# QSFP_Jumper.net
KiCad netlist of a schematic drawn in Altium Designer
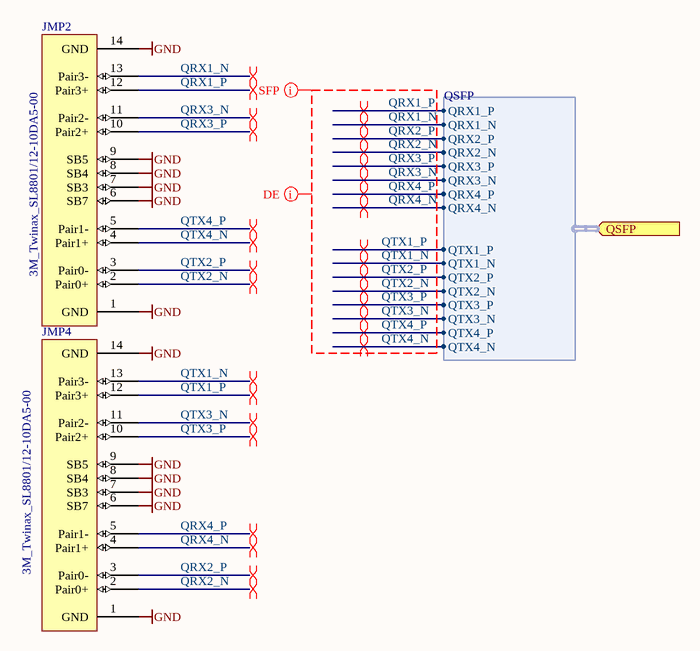
[diagram p0: QSFP_Jumper.SchDoc]

(export (version "E")
  (design (tool "Eeschema 10.0.6"))
  (components
    (comp (ref "JMP2")
      (value "3M_Twinax_SL8801/12-10DA5-00")
      (footprint "3M_Twinax_SL8801/12-10DA5-00")
      (libsource (lib "LIBRARY_SCH") (part "CBL_TWINAX_3M_4pairs_SB"))
    )
    (comp (ref "JMP4")
      (value "3M_Twinax_SL8801/12-10DA5-00")
      (footprint "3M_Twinax_SL8801/12-10DA5-00")
      (libsource (lib "LIBRARY_SCH") (part "CBL_TWINAX_3M_4pairs_SB"))
    )
  )
  (nets
    (net (code "2") (name "/QRX1_N") (class "Default")
      (node (ref "JMP2") (pin "13") (pinfunction "Pair3-_13") (pintype "bidirectional"))
    )
    (net (code "3") (name "/QRX1_P") (class "Default")
      (node (ref "JMP2") (pin "12") (pinfunction "Pair3+_12") (pintype "bidirectional"))
    )
    (net (code "4") (name "/QRX2_N") (class "Default")
      (node (ref "JMP4") (pin "2") (pinfunction "Pair0+_2") (pintype "bidirectional"))
    )
    (net (code "5") (name "/QRX2_P") (class "Default")
      (node (ref "JMP4") (pin "3") (pinfunction "Pair0-_3") (pintype "bidirectional"))
    )
    (net (code "6") (name "/QRX3_N") (class "Default")
      (node (ref "JMP2") (pin "11") (pinfunction "Pair2-_11") (pintype "bidirectional"))
    )
    (net (code "7") (name "/QRX3_P") (class "Default")
      (node (ref "JMP2") (pin "10") (pinfunction "Pair2+_10") (pintype "bidirectional"))
    )
    (net (code "8") (name "/QRX4_N") (class "Default")
      (node (ref "JMP4") (pin "4") (pinfunction "Pair1+_4") (pintype "bidirectional"))
    )
    (net (code "9") (name "/QRX4_P") (class "Default")
      (node (ref "JMP4") (pin "5") (pinfunction "Pair1-_5") (pintype "bidirectional"))
    )
    (net (code "10") (name "/QTX1_N") (class "Default")
      (node (ref "JMP4") (pin "13") (pinfunction "Pair3-_13") (pintype "bidirectional"))
    )
    (net (code "11") (name "/QTX1_P") (class "Default")
      (node (ref "JMP4") (pin "12") (pinfunction "Pair3+_12") (pintype "bidirectional"))
    )
    (net (code "12") (name "/QTX2_N") (class "Default")
      (node (ref "JMP2") (pin "2") (pinfunction "Pair0+_2") (pintype "bidirectional"))
    )
    (net (code "13") (name "/QTX2_P") (class "Default")
      (node (ref "JMP2") (pin "3") (pinfunction "Pair0-_3") (pintype "bidirectional"))
    )
    (net (code "14") (name "/QTX3_N") (class "Default")
      (node (ref "JMP4") (pin "11") (pinfunction "Pair2-_11") (pintype "bidirectional"))
    )
    (net (code "15") (name "/QTX3_P") (class "Default")
      (node (ref "JMP4") (pin "10") (pinfunction "Pair2+_10") (pintype "bidirectional"))
    )
    (net (code "16") (name "/QTX4_N") (class "Default")
      (node (ref "JMP2") (pin "4") (pinfunction "Pair1+_4") (pintype "bidirectional"))
    )
    (net (code "17") (name "/QTX4_P") (class "Default")
      (node (ref "JMP2") (pin "5") (pinfunction "Pair1-_5") (pintype "bidirectional"))
    )
    (net (code "19") (name "GND") (class "Default")
      (node (ref "JMP2") (pin "1") (pinfunction "GND_1") (pintype "power_in"))
      (node (ref "JMP2") (pin "14") (pinfunction "GND_14") (pintype "power_in"))
      (node (ref "JMP2") (pin "6") (pinfunction "SB7_6") (pintype "bidirectional"))
      (node (ref "JMP2") (pin "7") (pinfunction "SB3_7") (pintype "bidirectional"))
      (node (ref "JMP2") (pin "8") (pinfunction "SB4_8") (pintype "bidirectional"))
      (node (ref "JMP2") (pin "9") (pinfunction "SB5_9") (pintype "bidirectional"))
      (node (ref "JMP4") (pin "1") (pinfunction "GND_1") (pintype "power_in"))
      (node (ref "JMP4") (pin "14") (pinfunction "GND_14") (pintype "power_in"))
      (node (ref "JMP4") (pin "6") (pinfunction "SB7_6") (pintype "bidirectional"))
      (node (ref "JMP4") (pin "7") (pinfunction "SB3_7") (pintype "bidirectional"))
      (node (ref "JMP4") (pin "8") (pinfunction "SB4_8") (pintype "bidirectional"))
      (node (ref "JMP4") (pin "9") (pinfunction "SB5_9") (pintype "bidirectional"))
    )
  )
)
